# akabeacon_square_type2.net
KiCad netlist of a schematic drawn in EAGLE
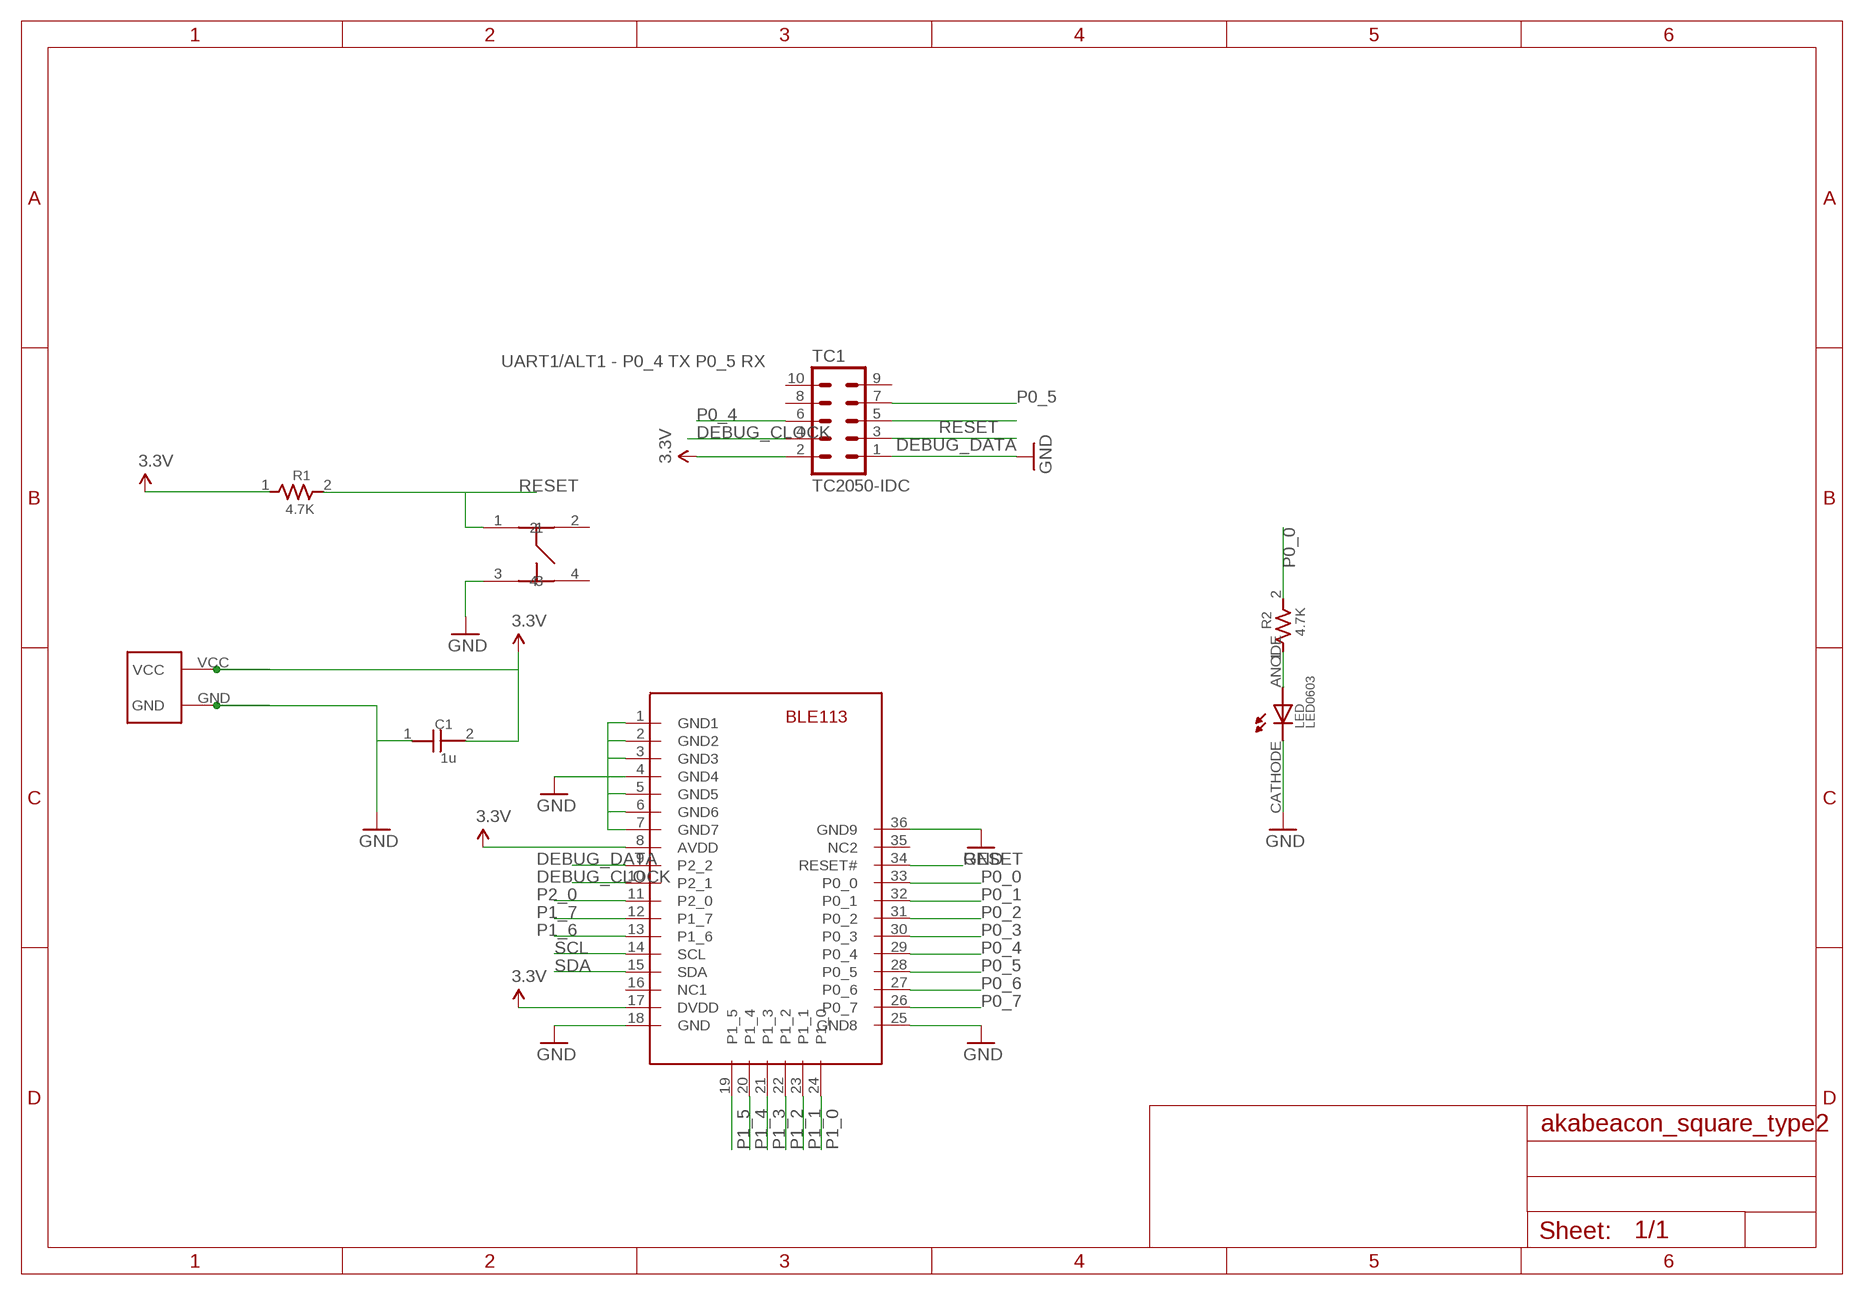
[diagram p0: schematic, sheet 1]

(export (version "E")
  (design (tool "Eeschema 10.0.6"))
  (components
    (comp (ref "C1")
      (value "1u")
      (footprint "eagle-import:0603")
      (libsource (lib "eagle-import") (part "CAPACITOR0603"))
    )
    (comp (ref "LED")
      (value "LED0603")
      (footprint "eagle-import:0603")
      (libsource (lib "eagle-import") (part "LED0603"))
    )
    (comp (ref "R1")
      (value "4.7K")
      (footprint "eagle-import:0603")
      (libsource (lib "eagle-import") (part "RESISTOR0603"))
    )
    (comp (ref "R2")
      (value "4.7K")
      (footprint "eagle-import:0603")
      (libsource (lib "eagle-import") (part "RESISTOR0603"))
    )
    (comp (ref "TC1")
      (value "TC2050-IDC")
      (footprint "eagle-import:TC2050-IDC-NL")
      (libsource (lib "eagle-import") (part "TC2050-IDC"))
    )
    (comp (ref "U$3")
      (value "SQUARE-TYPE2-TC2050")
      (footprint "eagle-import:SQUARE-TYPE2-TC2050")
      (libsource (lib "eagle-import") (part "SQUARE-TYPE2-TC2050"))
    )
    (comp (ref "U$5")
      (value "BLE113")
      (footprint "eagle-import:BLE113")
      (libsource (lib "eagle-import") (part "BLE113"))
    )
    (comp (ref "U$6")
      (value "SWICTH-4P(KMR2)")
      (footprint "eagle-import:SWITCH-4P(KMR2)")
      (libsource (lib "eagle-import") (part "SWICTH-4P(KMR2)"))
    )
  )
  (nets
    (net (code "1") (name "/DEBUG_CLOCK") (class "Default")
      (node (ref "TC1") (pin "4") (pinfunction "4_4") (pintype "passive"))
      (node (ref "U$5") (pin "10") (pinfunction "P2_1_10") (pintype "bidirectional"))
    )
    (net (code "2") (name "/DEBUG_DATA") (class "Default")
      (node (ref "TC1") (pin "3") (pinfunction "3_3") (pintype "passive"))
      (node (ref "U$5") (pin "9") (pinfunction "P2_2_9") (pintype "bidirectional"))
    )
    (net (code "3") (name "/P0_0") (class "Default")
      (node (ref "R2") (pin "2") (pinfunction "2_2") (pintype "passive"))
      (node (ref "U$5") (pin "33") (pinfunction "P0_0_33") (pintype "bidirectional"))
    )
    (net (code "4") (name "/P0_1") (class "Default")
      (node (ref "U$5") (pin "32") (pinfunction "P0_1_32") (pintype "bidirectional"))
    )
    (net (code "5") (name "/P0_2") (class "Default")
      (node (ref "U$5") (pin "31") (pinfunction "P0_2_31") (pintype "bidirectional"))
    )
    (net (code "6") (name "/P0_3") (class "Default")
      (node (ref "U$5") (pin "30") (pinfunction "P0_3_30") (pintype "bidirectional"))
    )
    (net (code "7") (name "/P0_4") (class "Default")
      (node (ref "TC1") (pin "6") (pinfunction "6_6") (pintype "passive"))
      (node (ref "U$5") (pin "29") (pinfunction "P0_4_29") (pintype "bidirectional"))
    )
    (net (code "8") (name "/P0_5") (class "Default")
      (node (ref "TC1") (pin "7") (pinfunction "7_7") (pintype "passive"))
      (node (ref "U$5") (pin "28") (pinfunction "P0_5_28") (pintype "bidirectional"))
    )
    (net (code "9") (name "/P0_6") (class "Default")
      (node (ref "U$5") (pin "27") (pinfunction "P0_6_27") (pintype "bidirectional"))
    )
    (net (code "10") (name "/P0_7") (class "Default")
      (node (ref "U$5") (pin "26") (pinfunction "P0_7_26") (pintype "bidirectional"))
    )
    (net (code "11") (name "/P1_0") (class "Default")
      (node (ref "U$5") (pin "24") (pinfunction "P1_0_24") (pintype "bidirectional"))
    )
    (net (code "12") (name "/P1_1") (class "Default")
      (node (ref "U$5") (pin "23") (pinfunction "P1_1_23") (pintype "bidirectional"))
    )
    (net (code "13") (name "/P1_2") (class "Default")
      (node (ref "U$5") (pin "22") (pinfunction "P1_2_22") (pintype "bidirectional"))
    )
    (net (code "14") (name "/P1_3") (class "Default")
      (node (ref "U$5") (pin "21") (pinfunction "P1_3_21") (pintype "bidirectional"))
    )
    (net (code "15") (name "/P1_4") (class "Default")
      (node (ref "U$5") (pin "20") (pinfunction "P1_4_20") (pintype "bidirectional"))
    )
    (net (code "16") (name "/P1_5") (class "Default")
      (node (ref "U$5") (pin "19") (pinfunction "P1_5_19") (pintype "bidirectional"))
    )
    (net (code "17") (name "/P1_6") (class "Default")
      (node (ref "U$5") (pin "13") (pinfunction "P1_6_13") (pintype "bidirectional"))
    )
    (net (code "18") (name "/P1_7") (class "Default")
      (node (ref "U$5") (pin "12") (pinfunction "P1_7_12") (pintype "bidirectional"))
    )
    (net (code "19") (name "/P2_0") (class "Default")
      (node (ref "U$5") (pin "11") (pinfunction "P2_0_11") (pintype "bidirectional"))
    )
    (net (code "20") (name "/RESET") (class "Default")
      (node (ref "R1") (pin "2") (pinfunction "2_2") (pintype "passive"))
      (node (ref "TC1") (pin "5") (pinfunction "5_5") (pintype "passive"))
      (node (ref "U$5") (pin "34") (pinfunction "RESET#_34") (pintype "bidirectional"))
      (node (ref "U$6") (pin "1") (pinfunction "1_1") (pintype "bidirectional"))
    )
    (net (code "21") (name "/SCL") (class "Default")
      (node (ref "U$5") (pin "14") (pinfunction "SCL_14") (pintype "bidirectional"))
    )
    (net (code "22") (name "/SDA") (class "Default")
      (node (ref "U$5") (pin "15") (pinfunction "SDA_15") (pintype "bidirectional"))
    )
    (net (code "23") (name "3.3V") (class "Default")
      (node (ref "C1") (pin "2") (pinfunction "2_2") (pintype "passive"))
      (node (ref "R1") (pin "1") (pinfunction "1_1") (pintype "passive"))
      (node (ref "TC1") (pin "2") (pinfunction "2_2") (pintype "passive"))
      (node (ref "U$3") (pin "VCC") (pinfunction "VCC_VCC") (pintype "bidirectional"))
      (node (ref "U$5") (pin "17") (pinfunction "DVDD_17") (pintype "bidirectional"))
      (node (ref "U$5") (pin "8") (pinfunction "AVDD_8") (pintype "bidirectional"))
    )
    (net (code "24") (name "GND") (class "Default")
      (node (ref "C1") (pin "1") (pinfunction "1_1") (pintype "passive"))
      (node (ref "LED") (pin "CATHODE") (pinfunction "CATHODE_CATHODE") (pintype "passive"))
      (node (ref "TC1") (pin "1") (pinfunction "1_1") (pintype "passive"))
      (node (ref "U$3") (pin "GND") (pinfunction "GND_GND") (pintype "bidirectional"))
      (node (ref "U$5") (pin "1") (pinfunction "GND1_1") (pintype "bidirectional"))
      (node (ref "U$5") (pin "18") (pinfunction "GND_18") (pintype "bidirectional"))
      (node (ref "U$5") (pin "2") (pinfunction "GND2_2") (pintype "bidirectional"))
      (node (ref "U$5") (pin "25") (pinfunction "GND8_25") (pintype "bidirectional"))
      (node (ref "U$5") (pin "3") (pinfunction "GND3_3") (pintype "bidirectional"))
      (node (ref "U$5") (pin "36") (pinfunction "GND9_36") (pintype "bidirectional"))
      (node (ref "U$5") (pin "4") (pinfunction "GND4_4") (pintype "bidirectional"))
      (node (ref "U$5") (pin "5") (pinfunction "GND5_5") (pintype "bidirectional"))
      (node (ref "U$5") (pin "6") (pinfunction "GND6_6") (pintype "bidirectional"))
      (node (ref "U$5") (pin "7") (pinfunction "GND7_7") (pintype "bidirectional"))
      (node (ref "U$6") (pin "3") (pinfunction "3_3") (pintype "bidirectional"))
    )
    (net (code "25") (name "Net-(LED-PadANODE)") (class "Default")
      (node (ref "LED") (pin "ANODE") (pinfunction "ANODE_ANODE") (pintype "passive"))
      (node (ref "R2") (pin "1") (pinfunction "1_1") (pintype "passive"))
    )
    (net (code "26") (name "unconnected-(TC1-Pad8)") (class "Default")
      (node (ref "TC1") (pin "8") (pinfunction "8_8") (pintype "passive"))
    )
    (net (code "27") (name "unconnected-(TC1-Pad9)") (class "Default")
      (node (ref "TC1") (pin "9") (pinfunction "9_9") (pintype "passive"))
    )
    (net (code "28") (name "unconnected-(TC1-Pad10)") (class "Default")
      (node (ref "TC1") (pin "10") (pinfunction "10_10") (pintype "passive"))
    )
    (net (code "29") (name "unconnected-(U$5-NC1-Pad16)") (class "Default")
      (node (ref "U$5") (pin "16") (pinfunction "NC1_16") (pintype "bidirectional"))
    )
    (net (code "30") (name "unconnected-(U$5-NC2-Pad35)") (class "Default")
      (node (ref "U$5") (pin "35") (pinfunction "NC2_35") (pintype "bidirectional"))
    )
    (net (code "31") (name "unconnected-(U$6-Pad2)") (class "Default")
      (node (ref "U$6") (pin "2") (pinfunction "2_2") (pintype "bidirectional"))
    )
    (net (code "32") (name "unconnected-(U$6-Pad4)") (class "Default")
      (node (ref "U$6") (pin "4") (pinfunction "4_4") (pintype "bidirectional"))
    )
  )
)
